# ng-beacon-mdbt42.net
KiCad netlist of a schematic drawn in EAGLE
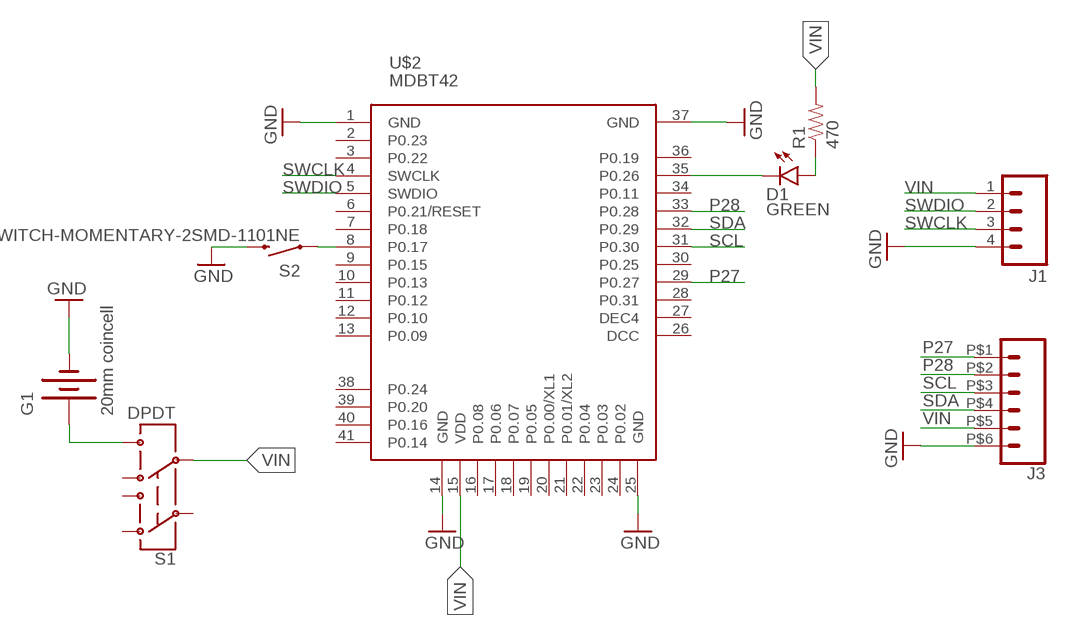
[diagram p0: schematic, sheet 1]

(export (version "E")
  (design (tool "Eeschema 10.0.6"))
  (components
    (comp (ref "D1")
      (value "GREEN")
      (footprint "eagle-import:LED-0603")
      (libsource (lib "eagle-import") (part "LED-GREEN0603"))
    )
    (comp (ref "G1")
      (value "20mm coincell")
      (footprint "eagle-import:BATTCON_20MM_4LEGS")
      (libsource (lib "eagle-import") (part "BATTERY20MM_4LEGS"))
    )
    (comp (ref "J1")
      (value "M04LOCK")
      (footprint "eagle-import:1X04_LOCK")
      (libsource (lib "eagle-import") (part "M04LOCK"))
    )
    (comp (ref "J3")
      (value "CONN_06")
      (footprint "eagle-import:PROTO4X6")
      (libsource (lib "eagle-import") (part "CONN_06"))
    )
    (comp (ref "R1")
      (value "470")
      (footprint "eagle-import:0603-RES")
      (libsource (lib "eagle-import") (part "470OHM1/10W1%(0603)"))
    )
    (comp (ref "S1")
      (value "DPDT")
      (footprint "eagle-import:AYZ0202")
      (libsource (lib "eagle-import") (part "SWITCH-DPDTAYZ0202"))
    )
    (comp (ref "S2")
      (value "SWITCH-MOMENTARY-2SMD-1101NE")
      (footprint "eagle-import:TACTILE-SWITCH-1101NE")
      (libsource (lib "eagle-import") (part "SWITCH-MOMENTARY-2SMD-1101NE"))
    )
    (comp (ref "U$2")
      (value "MDBT42")
      (footprint "eagle-import:MDBT42")
      (libsource (lib "eagle-import") (part "MDBT42"))
    )
  )
  (nets
    (net (code "1") (name "/P27") (class "Default")
      (node (ref "J3") (pin "P$1") (pinfunction "1_P$1") (pintype "passive"))
      (node (ref "U$2") (pin "29") (pinfunction "P0.27_29") (pintype "bidirectional"))
    )
    (net (code "2") (name "/P28") (class "Default")
      (node (ref "J3") (pin "P$2") (pinfunction "2_P$2") (pintype "passive"))
      (node (ref "U$2") (pin "33") (pinfunction "P0.28_33") (pintype "bidirectional"))
    )
    (net (code "3") (name "/SCL") (class "Default")
      (node (ref "J3") (pin "P$3") (pinfunction "3_P$3") (pintype "passive"))
      (node (ref "U$2") (pin "31") (pinfunction "P0.30_31") (pintype "bidirectional"))
    )
    (net (code "4") (name "/SDA") (class "Default")
      (node (ref "J3") (pin "P$4") (pinfunction "4_P$4") (pintype "passive"))
      (node (ref "U$2") (pin "32") (pinfunction "P0.29_32") (pintype "bidirectional"))
    )
    (net (code "5") (name "/SWCLK") (class "Default")
      (node (ref "J1") (pin "3") (pinfunction "3_3") (pintype "passive"))
      (node (ref "U$2") (pin "4") (pinfunction "SWCLK_4") (pintype "bidirectional"))
    )
    (net (code "6") (name "/SWDIO") (class "Default")
      (node (ref "J1") (pin "2") (pinfunction "2_2") (pintype "passive"))
      (node (ref "U$2") (pin "5") (pinfunction "SWDIO_5") (pintype "bidirectional"))
    )
    (net (code "7") (name "GND") (class "Default")
      (node (ref "G1") (pin "NEGATIVE") (pinfunction "-_NEGATIVE") (pintype "power_in"))
      (node (ref "J1") (pin "4") (pinfunction "4_4") (pintype "passive"))
      (node (ref "J3") (pin "P$6") (pinfunction "6_P$6") (pintype "passive"))
      (node (ref "S2") (pin "2") (pinfunction "2_2") (pintype "passive"))
      (node (ref "U$2") (pin "1") (pinfunction "GND_1") (pintype "bidirectional"))
      (node (ref "U$2") (pin "14") (pinfunction "GND_14") (pintype "bidirectional"))
      (node (ref "U$2") (pin "25") (pinfunction "GND_25") (pintype "bidirectional"))
      (node (ref "U$2") (pin "37") (pinfunction "GND_37") (pintype "bidirectional"))
    )
    (net (code "8") (name "Net-(D1-PadA)") (class "Default")
      (node (ref "D1") (pin "A") (pinfunction "A_A") (pintype "passive"))
      (node (ref "R1") (pin "1") (pinfunction "1_1") (pintype "passive"))
    )
    (net (code "9") (name "Net-(G1-+-PadPOSITIVE@1)") (class "Default")
      (node (ref "G1") (pin "POSITIVE@1") (pinfunction "+_POSITIVE@1") (pintype "power_in"))
      (node (ref "G1") (pin "POSITIVE@2") (pinfunction "+_POSITIVE@2") (pintype "power_in"))
      (node (ref "G1") (pin "POSITIVE@3") (pinfunction "+_POSITIVE@3") (pintype "power_in"))
      (node (ref "G1") (pin "POSITIVE@4") (pinfunction "+_POSITIVE@4") (pintype "power_in"))
      (node (ref "S1") (pin "6") (pinfunction "6_6") (pintype "bidirectional"))
    )
    (net (code "10") (name "Net-(U$2-P0.17)") (class "Default")
      (node (ref "S2") (pin "1") (pinfunction "1_1") (pintype "passive"))
      (node (ref "U$2") (pin "8") (pinfunction "P0.17_8") (pintype "bidirectional"))
    )
    (net (code "11") (name "Net-(U$2-P0.26)") (class "Default")
      (node (ref "D1") (pin "C") (pinfunction "C_C") (pintype "passive"))
      (node (ref "U$2") (pin "35") (pinfunction "P0.26_35") (pintype "bidirectional"))
    )
    (net (code "12") (name "VIN") (class "Default")
      (node (ref "J1") (pin "1") (pinfunction "1_1") (pintype "passive"))
      (node (ref "J3") (pin "P$5") (pinfunction "5_P$5") (pintype "passive"))
      (node (ref "R1") (pin "2") (pinfunction "2_2") (pintype "passive"))
      (node (ref "S1") (pin "5") (pinfunction "5_5") (pintype "bidirectional"))
      (node (ref "U$2") (pin "15") (pinfunction "VDD_15") (pintype "bidirectional"))
    )
    (net (code "13") (name "unconnected-(S1-Pad1)") (class "Default")
      (node (ref "S1") (pin "1") (pinfunction "1_1") (pintype "bidirectional"))
    )
    (net (code "14") (name "unconnected-(S1-Pad2)") (class "Default")
      (node (ref "S1") (pin "2") (pinfunction "2_2") (pintype "bidirectional"))
    )
    (net (code "15") (name "unconnected-(S1-Pad3)") (class "Default")
      (node (ref "S1") (pin "3") (pinfunction "3_3") (pintype "bidirectional"))
    )
    (net (code "16") (name "unconnected-(S1-Pad4)") (class "Default")
      (node (ref "S1") (pin "4") (pinfunction "4_4") (pintype "bidirectional"))
    )
    (net (code "17") (name "unconnected-(U$2-DCC-Pad26)") (class "Default")
      (node (ref "U$2") (pin "26") (pinfunction "DCC_26") (pintype "bidirectional"))
    )
    (net (code "18") (name "unconnected-(U$2-DEC4-Pad27)") (class "Default")
      (node (ref "U$2") (pin "27") (pinfunction "DEC4_27") (pintype "bidirectional"))
    )
    (net (code "19") (name "unconnected-(U$2-P0.00{slash}XL1-Pad20)") (class "Default")
      (node (ref "U$2") (pin "20") (pinfunction "P0.00/XL1_20") (pintype "bidirectional"))
    )
    (net (code "20") (name "unconnected-(U$2-P0.01{slash}XL2-Pad21)") (class "Default")
      (node (ref "U$2") (pin "21") (pinfunction "P0.01/XL2_21") (pintype "bidirectional"))
    )
    (net (code "21") (name "unconnected-(U$2-P0.02-Pad24)") (class "Default")
      (node (ref "U$2") (pin "24") (pinfunction "P0.02_24") (pintype "bidirectional"))
    )
    (net (code "22") (name "unconnected-(U$2-P0.03-Pad23)") (class "Default")
      (node (ref "U$2") (pin "23") (pinfunction "P0.03_23") (pintype "bidirectional"))
    )
    (net (code "23") (name "unconnected-(U$2-P0.04-Pad22)") (class "Default")
      (node (ref "U$2") (pin "22") (pinfunction "P0.04_22") (pintype "bidirectional"))
    )
    (net (code "24") (name "unconnected-(U$2-P0.05-Pad19)") (class "Default")
      (node (ref "U$2") (pin "19") (pinfunction "P0.05_19") (pintype "bidirectional"))
    )
    (net (code "25") (name "unconnected-(U$2-P0.06-Pad17)") (class "Default")
      (node (ref "U$2") (pin "17") (pinfunction "P0.06_17") (pintype "bidirectional"))
    )
    (net (code "26") (name "unconnected-(U$2-P0.07-Pad18)") (class "Default")
      (node (ref "U$2") (pin "18") (pinfunction "P0.07_18") (pintype "bidirectional"))
    )
    (net (code "27") (name "unconnected-(U$2-P0.08-Pad16)") (class "Default")
      (node (ref "U$2") (pin "16") (pinfunction "P0.08_16") (pintype "bidirectional"))
    )
    (net (code "28") (name "unconnected-(U$2-P0.09-Pad13)") (class "Default")
      (node (ref "U$2") (pin "13") (pinfunction "P0.09_13") (pintype "bidirectional"))
    )
    (net (code "29") (name "unconnected-(U$2-P0.10-Pad12)") (class "Default")
      (node (ref "U$2") (pin "12") (pinfunction "P0.10_12") (pintype "bidirectional"))
    )
    (net (code "30") (name "unconnected-(U$2-P0.11-Pad34)") (class "Default")
      (node (ref "U$2") (pin "34") (pinfunction "P0.11_34") (pintype "bidirectional"))
    )
    (net (code "31") (name "unconnected-(U$2-P0.12-Pad11)") (class "Default")
      (node (ref "U$2") (pin "11") (pinfunction "P0.12_11") (pintype "bidirectional"))
    )
    (net (code "32") (name "unconnected-(U$2-P0.13-Pad10)") (class "Default")
      (node (ref "U$2") (pin "10") (pinfunction "P0.13_10") (pintype "bidirectional"))
    )
    (net (code "33") (name "unconnected-(U$2-P0.14-Pad41)") (class "Default")
      (node (ref "U$2") (pin "41") (pinfunction "P0.14_41") (pintype "bidirectional"))
    )
    (net (code "34") (name "unconnected-(U$2-P0.15-Pad9)") (class "Default")
      (node (ref "U$2") (pin "9") (pinfunction "P0.15_9") (pintype "bidirectional"))
    )
    (net (code "35") (name "unconnected-(U$2-P0.16-Pad40)") (class "Default")
      (node (ref "U$2") (pin "40") (pinfunction "P0.16_40") (pintype "bidirectional"))
    )
    (net (code "36") (name "unconnected-(U$2-P0.18-Pad7)") (class "Default")
      (node (ref "U$2") (pin "7") (pinfunction "P0.18_7") (pintype "bidirectional"))
    )
    (net (code "37") (name "unconnected-(U$2-P0.19-Pad36)") (class "Default")
      (node (ref "U$2") (pin "36") (pinfunction "P0.19_36") (pintype "bidirectional"))
    )
    (net (code "38") (name "unconnected-(U$2-P0.20-Pad39)") (class "Default")
      (node (ref "U$2") (pin "39") (pinfunction "P0.20_39") (pintype "bidirectional"))
    )
    (net (code "39") (name "unconnected-(U$2-P0.21{slash}RESET-Pad6)") (class "Default")
      (node (ref "U$2") (pin "6") (pinfunction "P0.21/RESET_6") (pintype "bidirectional"))
    )
    (net (code "40") (name "unconnected-(U$2-P0.22-Pad3)") (class "Default")
      (node (ref "U$2") (pin "3") (pinfunction "P0.22_3") (pintype "bidirectional"))
    )
    (net (code "41") (name "unconnected-(U$2-P0.23-Pad2)") (class "Default")
      (node (ref "U$2") (pin "2") (pinfunction "P0.23_2") (pintype "bidirectional"))
    )
    (net (code "42") (name "unconnected-(U$2-P0.24-Pad38)") (class "Default")
      (node (ref "U$2") (pin "38") (pinfunction "P0.24_38") (pintype "bidirectional"))
    )
    (net (code "43") (name "unconnected-(U$2-P0.25-Pad30)") (class "Default")
      (node (ref "U$2") (pin "30") (pinfunction "P0.25_30") (pintype "bidirectional"))
    )
    (net (code "44") (name "unconnected-(U$2-P0.31-Pad28)") (class "Default")
      (node (ref "U$2") (pin "28") (pinfunction "P0.31_28") (pintype "bidirectional"))
    )
  )
)
